# FVA-NET.net
KiCad netlist of a schematic drawn in Altium Designer
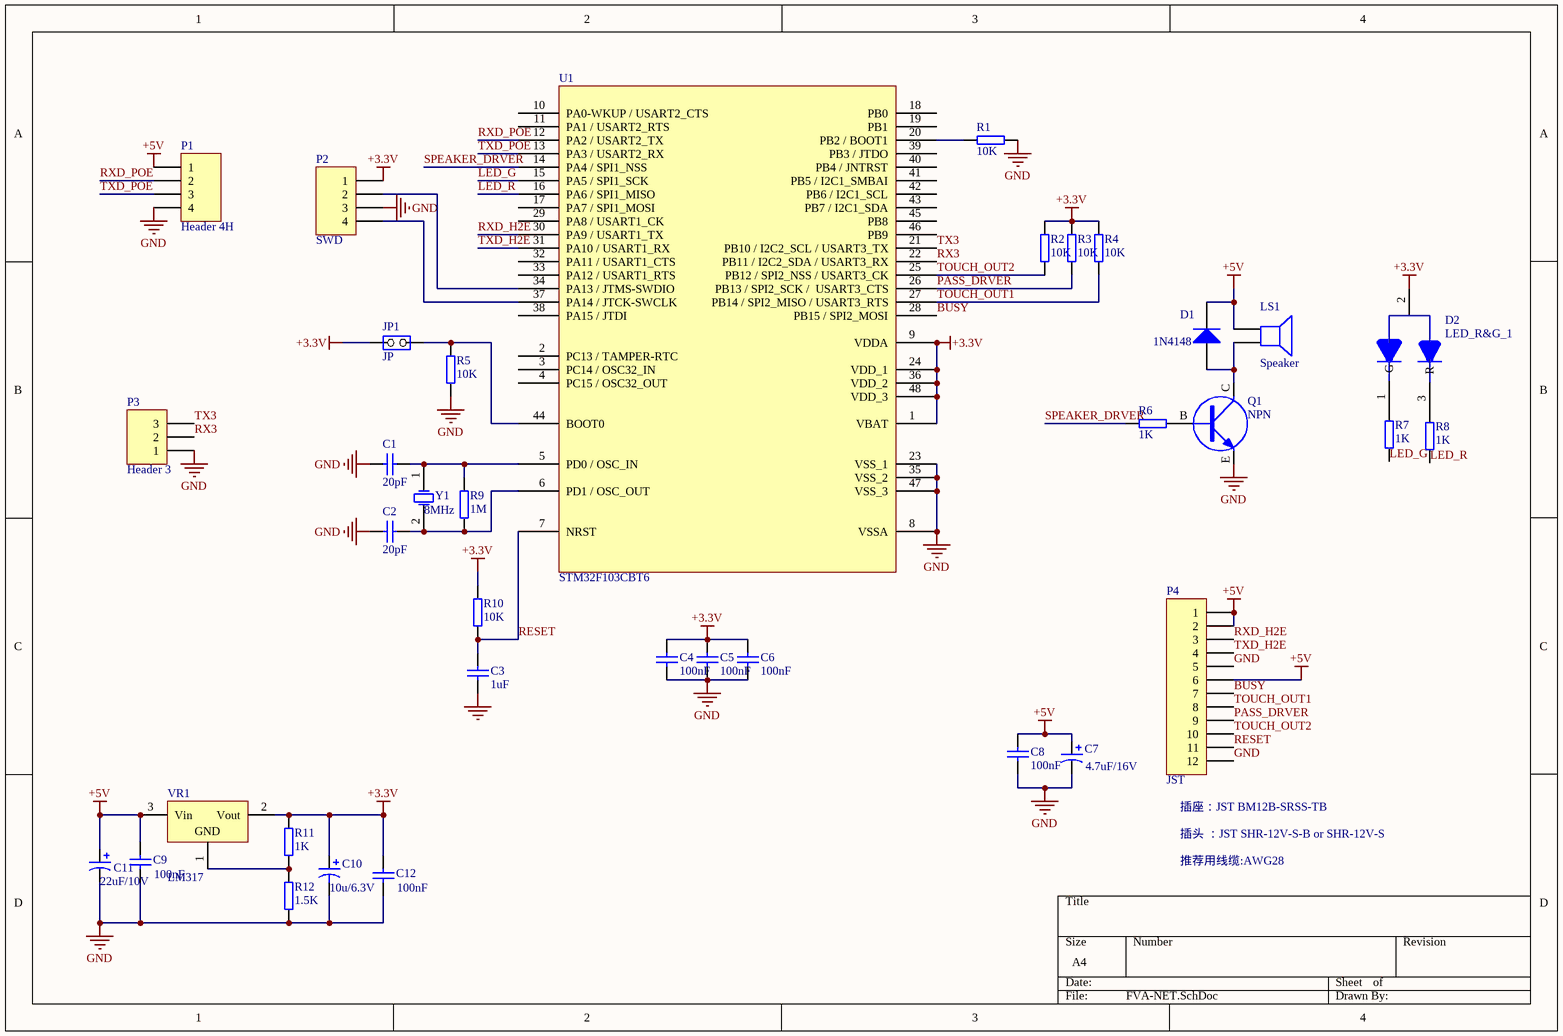
[diagram p0: FVA-NET.SchDoc]

(export (version "E")
  (design (tool "Eeschema 10.0.6"))
  (components
    (comp (ref "C1")
      (value "20pF")
      (footprint "c0603")
      (description "电容器 Capacitor")
      (fields (field (name "Comment") "Cap") (field (name "PUBLISHER") "Altium Limited"))
      (libsource (lib "电容器") (part "Cap"))
    )
    (comp (ref "C2")
      (value "20pF")
      (footprint "c0603")
      (description "电容器 Capacitor")
      (fields (field (name "Comment") "Cap") (field (name "PUBLISHER") "Altium Limited"))
      (libsource (lib "电容器") (part "Cap"))
    )
    (comp (ref "C3")
      (value "1uF")
      (footprint "c0603")
      (description "电容器 Capacitor")
      (fields (field (name "Comment") "Cap") (field (name "PUBLISHER") "Altium Limited"))
      (libsource (lib "电容器") (part "Cap"))
    )
    (comp (ref "C4")
      (value "100nF")
      (footprint "c0603")
      (description "电容器 Capacitor")
      (fields (field (name "Comment") "Cap") (field (name "PUBLISHER") "Altium Limited"))
      (libsource (lib "电容器") (part "Cap"))
    )
    (comp (ref "C5")
      (value "100nF")
      (footprint "c0603")
      (description "电容器 Capacitor")
      (fields (field (name "Comment") "Cap") (field (name "PUBLISHER") "Altium Limited"))
      (libsource (lib "电容器") (part "Cap"))
    )
    (comp (ref "C6")
      (value "100nF")
      (footprint "c0603")
      (description "电容器 Capacitor")
      (fields (field (name "Comment") "Cap") (field (name "PUBLISHER") "Altium Limited"))
      (libsource (lib "电容器") (part "Cap"))
    )
    (comp (ref "C7")
      (value "4.7uF/16V")
      (footprint "T3216")
      (fields (field (name "Comment") "CAP+"))
      (libsource (lib "PV") (part "CAP+"))
    )
    (comp (ref "C8")
      (value "100nF")
      (footprint "C0603")
      (description "Capacitor")
      (fields (field (name "Comment") "CAP"))
      (libsource (lib "PV") (part "CAP"))
    )
    (comp (ref "C9")
      (value "100nF")
      (footprint "C0603")
      (description "Capacitor")
      (fields (field (name "Comment") "cap"))
      (libsource (lib "PV") (part "CAP"))
    )
    (comp (ref "C10")
      (value "10u/6.3V")
      (footprint "T3216")
      (description "Polarized Capacitor (Radial)")
      (fields (field (name "Comment") "Cap Pol1") (field (name "PUBLISHER") "Altium Limited"))
      (libsource (lib "Miscellaneous Devices") (part "Cap Pol1"))
    )
    (comp (ref "C11")
      (value "22uF/10V")
      (footprint "T3216")
      (fields (field (name "Comment") "CAP+"))
      (libsource (lib "PV") (part "CAP+"))
    )
    (comp (ref "C12")
      (value "100nF")
      (footprint "C0603")
      (description "Capacitor")
      (fields (field (name "Comment") "cap"))
      (libsource (lib "PV") (part "CAP"))
    )
    (comp (ref "D1")
      (value "1N4148")
      (footprint "D1206")
      (description "High Conductance Fast Diode")
      (libsource (lib "Miscellaneous Devices") (part "Diode 1N4148"))
    )
    (comp (ref "D2") (value "LED_R&G_1") (footprint "LED_R&G") (libsource (lib "PV") (part "LED_R&G_1")))
    (comp (ref "JP1") (value "JP") (footprint "SIP2") (libsource (lib "开关和继电器") (part "JP2")))
    (comp (ref "LS1")
      (value "Speaker")
      (footprint "BUZZER")
      (description "Loudspeaker")
      (fields (field (name "PUBLISHER") "Altium Limited"))
      (libsource (lib "Miscellaneous Devices") (part "Speaker"))
    )
    (comp (ref "P1")
      (value "Header 4H")
      (footprint "HDR1X4H")
      (description "Header, 4-Pin, Right Angle")
      (fields (field (name "PUBLISHER") "Altium Limited"))
      (libsource (lib "Miscellaneous Connectors") (part "Header 4H"))
    )
    (comp (ref "P2")
      (value "SWD")
      (footprint "HDR1X4")
      (description "Header, 4-Pin")
      (fields (field (name "PUBLISHER") "Altium Limited"))
      (libsource (lib "Miscellaneous Connectors") (part "Header 4"))
    )
    (comp (ref "P3")
      (value "Header 3")
      (footprint "HDR1X3")
      (description "Header, 3-Pin")
      (fields (field (name "PUBLISHER") "Altium Limited"))
      (libsource (lib "Miscellaneous Connectors") (part "Header 3"))
    )
    (comp (ref "P4")
      (value "JST")
      (footprint "JST BM12B-SRSS-TB")
      (description "Header, 12-Pin")
      (fields (field (name "PUBLISHER") "Altium Limited"))
      (libsource (lib "Miscellaneous Connectors") (part "Header 12"))
    )
    (comp (ref "Q1")
      (value "NPN")
      (footprint "SOT23/BEC")
      (description "NPN Transistor")
      (libsource (lib "PV") (part "NPN"))
    )
    (comp (ref "R1")
      (value "10K")
      (footprint "R0603")
      (fields (field (name "Comment") "RES"))
      (libsource (lib "PV") (part "RES"))
    )
    (comp (ref "R2")
      (value "10K")
      (footprint "R0603")
      (fields (field (name "Comment") "RES"))
      (libsource (lib "PV") (part "RES"))
    )
    (comp (ref "R3")
      (value "10K")
      (footprint "R0603")
      (fields (field (name "Comment") "RES"))
      (libsource (lib "PV") (part "RES"))
    )
    (comp (ref "R4")
      (value "10K")
      (footprint "R0603")
      (fields (field (name "Comment") "RES"))
      (libsource (lib "PV") (part "RES"))
    )
    (comp (ref "R5")
      (value "10K")
      (footprint "R0603")
      (fields (field (name "Comment") "RES"))
      (libsource (lib "PV") (part "RES"))
    )
    (comp (ref "R6")
      (value "1K")
      (footprint "R0603")
      (fields (field (name "Comment") "RES"))
      (libsource (lib "PV") (part "RES"))
    )
    (comp (ref "R7")
      (value "1K")
      (footprint "R0603")
      (fields (field (name "Comment") "RES"))
      (libsource (lib "PV") (part "RES"))
    )
    (comp (ref "R8")
      (value "1K")
      (footprint "R0603")
      (fields (field (name "Comment") "RES"))
      (libsource (lib "PV") (part "RES"))
    )
    (comp (ref "R9")
      (value "1M")
      (footprint "R0603")
      (fields (field (name "Comment") "RES"))
      (libsource (lib "PV") (part "RES"))
    )
    (comp (ref "R10")
      (value "10K")
      (footprint "R0603")
      (fields (field (name "Comment") "RES"))
      (libsource (lib "PV") (part "RES"))
    )
    (comp (ref "R11")
      (value "1K")
      (footprint "R0603")
      (fields (field (name "Comment") "RES"))
      (libsource (lib "PV") (part "RES"))
    )
    (comp (ref "R12")
      (value "1.5K")
      (footprint "R0603")
      (fields (field (name "Comment") "RES"))
      (libsource (lib "PV") (part "RES"))
    )
    (comp (ref "U1")
      (value "STM32F103CBT6")
      (footprint "LQFP48")
      (description "48 pin")
      (libsource (lib "微控制器") (part "STM32F103x6x8xB"))
    )
    (comp (ref "VR1")
      (value "LM317")
      (footprint "SOT223")
      (description "Voltage Regulator")
      (fields (field (name "PUBLISHER") "Altium Limited"))
      (libsource (lib "FVA-NET") (part "Volt Reg"))
    )
    (comp (ref "Y1")
      (value "8MHz")
      (footprint "XTAL-HC-49/U-S")
      (description "Crystal Oscillator")
      (fields (field (name "PUBLISHER") "Altium Limited"))
      (libsource (lib "晶体_振荡器") (part "XTAL"))
    )
  )
  (nets
    (net (code "1") (name "+3.3V") (class "Default")
      (node (ref "C10") (pin "1") (pinfunction "1_1") (pintype "passive"))
      (node (ref "C12") (pin "2") (pinfunction "2_2") (pintype "passive"))
      (node (ref "C4") (pin "2") (pinfunction "2_2") (pintype "passive"))
      (node (ref "C5") (pin "2") (pinfunction "2_2") (pintype "passive"))
      (node (ref "C6") (pin "2") (pinfunction "2_2") (pintype "passive"))
      (node (ref "D2") (pin "2") (pinfunction "P_2") (pintype "passive"))
      (node (ref "JP1") (pin "1") (pinfunction "COMMON_1") (pintype "passive"))
      (node (ref "P2") (pin "1") (pinfunction "1_1") (pintype "passive"))
      (node (ref "R10") (pin "1") (pinfunction "1_1") (pintype "passive"))
      (node (ref "R11") (pin "2") (pinfunction "2_2") (pintype "passive"))
      (node (ref "R2") (pin "2") (pinfunction "2_2") (pintype "passive"))
      (node (ref "R3") (pin "2") (pinfunction "2_2") (pintype "passive"))
      (node (ref "R4") (pin "2") (pinfunction "2_2") (pintype "passive"))
      (node (ref "U1") (pin "1") (pinfunction "VBAT_1") (pintype "passive"))
      (node (ref "U1") (pin "24") (pinfunction "VDD_1_24") (pintype "passive"))
      (node (ref "U1") (pin "36") (pinfunction "VDD_2_36") (pintype "passive"))
      (node (ref "U1") (pin "48") (pinfunction "VDD_3_48") (pintype "passive"))
      (node (ref "U1") (pin "9") (pinfunction "VDDA_9") (pintype "passive"))
      (node (ref "VR1") (pin "2") (pinfunction "Vout_2") (pintype "passive"))
    )
    (net (code "2") (name "+5V") (class "Default")
      (node (ref "C11") (pin "1") (pinfunction "1_1") (pintype "passive"))
      (node (ref "C7") (pin "1") (pinfunction "1_1") (pintype "passive"))
      (node (ref "C8") (pin "2") (pinfunction "2_2") (pintype "passive"))
      (node (ref "C9") (pin "2") (pinfunction "2_2") (pintype "passive"))
      (node (ref "D1") (pin "2") (pinfunction "K_2") (pintype "passive"))
      (node (ref "LS1") (pin "1") (pinfunction "1_1") (pintype "passive"))
      (node (ref "P1") (pin "1") (pinfunction "1_1") (pintype "passive"))
      (node (ref "P4") (pin "1") (pinfunction "1_1") (pintype "passive"))
      (node (ref "P4") (pin "2") (pinfunction "2_2") (pintype "passive"))
      (node (ref "P4") (pin "6") (pinfunction "6_6") (pintype "passive"))
      (node (ref "VR1") (pin "3") (pinfunction "Vin_3") (pintype "passive"))
    )
    (net (code "3") (name "/BUSY") (class "Default")
      (node (ref "P4") (pin "7") (pinfunction "7_7") (pintype "passive"))
      (node (ref "U1") (pin "28") (pinfunction "PB15_/_SPI2_MOSI_28") (pintype "passive"))
    )
    (net (code "4") (name "/LED_G") (class "Default")
      (node (ref "R7") (pin "2") (pinfunction "2_2") (pintype "passive"))
      (node (ref "U1") (pin "15") (pinfunction "PA5_/_SPI1_SCK_15") (pintype "passive"))
    )
    (net (code "5") (name "/LED_R") (class "Default")
      (node (ref "R8") (pin "2") (pinfunction "2_2") (pintype "passive"))
      (node (ref "U1") (pin "16") (pinfunction "PA6_/_SPI1_MISO_16") (pintype "passive"))
    )
    (net (code "6") (name "/PASS_DRVER") (class "Default")
      (node (ref "P4") (pin "9") (pinfunction "9_9") (pintype "passive"))
      (node (ref "R3") (pin "1") (pinfunction "1_1") (pintype "passive"))
      (node (ref "U1") (pin "26") (pinfunction "PB13_/_SPI2_SCK_/__USART3_CTS_26") (pintype "passive"))
    )
    (net (code "7") (name "/RESET") (class "Default")
      (node (ref "C3") (pin "2") (pinfunction "2_2") (pintype "passive"))
      (node (ref "P4") (pin "11") (pinfunction "11_11") (pintype "passive"))
      (node (ref "R10") (pin "2") (pinfunction "2_2") (pintype "passive"))
      (node (ref "U1") (pin "7") (pinfunction "NRST_7") (pintype "passive"))
    )
    (net (code "8") (name "/RX3") (class "Default")
      (node (ref "P3") (pin "2") (pinfunction "2_2") (pintype "passive"))
      (node (ref "U1") (pin "22") (pinfunction "PB11_/_I2C2_SDA_/_USART3_RX_22") (pintype "passive"))
    )
    (net (code "9") (name "/RXD_H2E") (class "Default")
      (node (ref "P4") (pin "3") (pinfunction "3_3") (pintype "passive"))
      (node (ref "U1") (pin "30") (pinfunction "PA9_/_USART1_TX_30") (pintype "passive"))
    )
    (net (code "10") (name "/RXD_POE") (class "Default")
      (node (ref "P1") (pin "2") (pinfunction "2_2") (pintype "passive"))
      (node (ref "U1") (pin "12") (pinfunction "PA2_/_USART2_TX_12") (pintype "passive"))
    )
    (net (code "11") (name "/SPEAKER_DRVER") (class "Default")
      (node (ref "R6") (pin "2") (pinfunction "2_2") (pintype "passive"))
      (node (ref "U1") (pin "14") (pinfunction "PA4_/_SPI1_NSS_14") (pintype "passive"))
    )
    (net (code "12") (name "/TOUCH_OUT1") (class "Default")
      (node (ref "P4") (pin "8") (pinfunction "8_8") (pintype "passive"))
      (node (ref "R4") (pin "1") (pinfunction "1_1") (pintype "passive"))
      (node (ref "U1") (pin "27") (pinfunction "PB14_/_SPI2_MISO_/_USART3_RTS_27") (pintype "passive"))
    )
    (net (code "13") (name "/TOUCH_OUT2") (class "Default")
      (node (ref "P4") (pin "10") (pinfunction "10_10") (pintype "passive"))
      (node (ref "R2") (pin "1") (pinfunction "1_1") (pintype "passive"))
      (node (ref "U1") (pin "25") (pinfunction "PB12_/_SPI2_NSS_/_USART3_CK_25") (pintype "passive"))
    )
    (net (code "14") (name "/TX3") (class "Default")
      (node (ref "P3") (pin "3") (pinfunction "3_3") (pintype "passive"))
      (node (ref "U1") (pin "21") (pinfunction "PB10_/_I2C2_SCL_/_USART3_TX_21") (pintype "passive"))
    )
    (net (code "15") (name "/TXD_H2E") (class "Default")
      (node (ref "P4") (pin "4") (pinfunction "4_4") (pintype "passive"))
      (node (ref "U1") (pin "31") (pinfunction "PA10_/_USART1_RX_31") (pintype "passive"))
    )
    (net (code "16") (name "/TXD_POE") (class "Default")
      (node (ref "P1") (pin "3") (pinfunction "3_3") (pintype "passive"))
      (node (ref "U1") (pin "13") (pinfunction "PA3_/_USART2_RX_13") (pintype "passive"))
    )
    (net (code "17") (name "GND") (class "Default")
      (node (ref "C1") (pin "1") (pinfunction "1_1") (pintype "passive"))
      (node (ref "C10") (pin "2") (pinfunction "2_2") (pintype "passive"))
      (node (ref "C11") (pin "2") (pinfunction "2_2") (pintype "passive"))
      (node (ref "C12") (pin "1") (pinfunction "1_1") (pintype "passive"))
      (node (ref "C2") (pin "1") (pinfunction "1_1") (pintype "passive"))
      (node (ref "C3") (pin "1") (pinfunction "1_1") (pintype "passive"))
      (node (ref "C4") (pin "1") (pinfunction "1_1") (pintype "passive"))
      (node (ref "C5") (pin "1") (pinfunction "1_1") (pintype "passive"))
      (node (ref "C6") (pin "1") (pinfunction "1_1") (pintype "passive"))
      (node (ref "C7") (pin "2") (pinfunction "2_2") (pintype "passive"))
      (node (ref "C8") (pin "1") (pinfunction "1_1") (pintype "passive"))
      (node (ref "C9") (pin "1") (pinfunction "1_1") (pintype "passive"))
      (node (ref "P1") (pin "4") (pinfunction "4_4") (pintype "passive"))
      (node (ref "P2") (pin "3") (pinfunction "3_3") (pintype "passive"))
      (node (ref "P3") (pin "1") (pinfunction "1_1") (pintype "passive"))
      (node (ref "P4") (pin "12") (pinfunction "12_12") (pintype "passive"))
      (node (ref "P4") (pin "5") (pinfunction "5_5") (pintype "passive"))
      (node (ref "Q1") (pin "E") (pinfunction "E_E") (pintype "passive"))
      (node (ref "R1") (pin "1") (pinfunction "1_1") (pintype "passive"))
      (node (ref "R12") (pin "1") (pinfunction "1_1") (pintype "passive"))
      (node (ref "R5") (pin "1") (pinfunction "1_1") (pintype "passive"))
      (node (ref "U1") (pin "23") (pinfunction "VSS_1_23") (pintype "passive"))
      (node (ref "U1") (pin "35") (pinfunction "VSS_2_35") (pintype "passive"))
      (node (ref "U1") (pin "47") (pinfunction "VSS_3_47") (pintype "passive"))
      (node (ref "U1") (pin "8") (pinfunction "VSSA_8") (pintype "passive"))
    )
    (net (code "18") (name "Net-(D1-A)") (class "Default")
      (node (ref "D1") (pin "1") (pinfunction "A_1") (pintype "passive"))
      (node (ref "LS1") (pin "2") (pinfunction "2_2") (pintype "passive"))
      (node (ref "Q1") (pin "C") (pinfunction "C_C") (pintype "passive"))
    )
    (net (code "19") (name "Net-(D2-G)") (class "Default")
      (node (ref "D2") (pin "1") (pinfunction "G_1") (pintype "passive"))
      (node (ref "R7") (pin "1") (pinfunction "1_1") (pintype "passive"))
    )
    (net (code "20") (name "Net-(D2-R)") (class "Default")
      (node (ref "D2") (pin "3") (pinfunction "R_3") (pintype "passive"))
      (node (ref "R8") (pin "1") (pinfunction "1_1") (pintype "passive"))
    )
    (net (code "21") (name "Net-(JP1-NO)") (class "Default")
      (node (ref "JP1") (pin "2") (pinfunction "NO_2") (pintype "passive"))
      (node (ref "R5") (pin "2") (pinfunction "2_2") (pintype "passive"))
      (node (ref "U1") (pin "44") (pinfunction "BOOT0_44") (pintype "passive"))
    )
    (net (code "22") (name "Net-(Q1-PadB)") (class "Default")
      (node (ref "Q1") (pin "B") (pinfunction "B_B") (pintype "passive"))
      (node (ref "R6") (pin "1") (pinfunction "1_1") (pintype "passive"))
    )
    (net (code "23") (name "Net-(U1-PA13_{slash}_JTMS-SWDIO)") (class "Default")
      (node (ref "P2") (pin "2") (pinfunction "2_2") (pintype "passive"))
      (node (ref "U1") (pin "34") (pinfunction "PA13_/_JTMS-SWDIO_34") (pintype "passive"))
    )
    (net (code "24") (name "Net-(U1-PA14_{slash}_JTCK-SWCLK)") (class "Default")
      (node (ref "P2") (pin "4") (pinfunction "4_4") (pintype "passive"))
      (node (ref "U1") (pin "37") (pinfunction "PA14_/_JTCK-SWCLK_37") (pintype "passive"))
    )
    (net (code "25") (name "Net-(U1-PB2_{slash}_BOOT1)") (class "Default")
      (node (ref "R1") (pin "2") (pinfunction "2_2") (pintype "passive"))
      (node (ref "U1") (pin "20") (pinfunction "PB2_/_BOOT1_20") (pintype "passive"))
    )
    (net (code "26") (name "Net-(U1-PD0_{slash}_OSC_IN)") (class "Default")
      (node (ref "C1") (pin "2") (pinfunction "2_2") (pintype "passive"))
      (node (ref "R9") (pin "2") (pinfunction "2_2") (pintype "passive"))
      (node (ref "U1") (pin "5") (pinfunction "PD0_/_OSC_IN_5") (pintype "passive"))
      (node (ref "Y1") (pin "1") (pinfunction "OSC1_1") (pintype "passive"))
    )
    (net (code "27") (name "Net-(U1-PD1_{slash}_OSC_OUT)") (class "Default")
      (node (ref "C2") (pin "2") (pinfunction "2_2") (pintype "passive"))
      (node (ref "R9") (pin "1") (pinfunction "1_1") (pintype "passive"))
      (node (ref "U1") (pin "6") (pinfunction "PD1_/_OSC_OUT_6") (pintype "passive"))
      (node (ref "Y1") (pin "2") (pinfunction "OSC2_2") (pintype "passive"))
    )
    (net (code "28") (name "Net-(VR1-GND)") (class "Default")
      (node (ref "R11") (pin "1") (pinfunction "1_1") (pintype "passive"))
      (node (ref "R12") (pin "2") (pinfunction "2_2") (pintype "passive"))
      (node (ref "VR1") (pin "1") (pinfunction "GND_1") (pintype "passive"))
    )
    (net (code "29") (name "unconnected-(U1-PA0-WKUP_{slash}_USART2_CTS-Pad10)") (class "Default")
      (node (ref "U1") (pin "10") (pinfunction "PA0-WKUP_/_USART2_CTS_10") (pintype "passive"))
    )
    (net (code "30") (name "unconnected-(U1-PA1_{slash}_USART2_RTS-Pad11)") (class "Default")
      (node (ref "U1") (pin "11") (pinfunction "PA1_/_USART2_RTS_11") (pintype "passive"))
    )
    (net (code "31") (name "unconnected-(U1-PA7_{slash}_SPI1_MOSI-Pad17)") (class "Default")
      (node (ref "U1") (pin "17") (pinfunction "PA7_/_SPI1_MOSI_17") (pintype "passive"))
    )
    (net (code "32") (name "unconnected-(U1-PA8_{slash}_USART1_CK-Pad29)") (class "Default")
      (node (ref "U1") (pin "29") (pinfunction "PA8_/_USART1_CK_29") (pintype "passive"))
    )
    (net (code "33") (name "unconnected-(U1-PA11_{slash}_USART1_CTS-Pad32)") (class "Default")
      (node (ref "U1") (pin "32") (pinfunction "PA11_/_USART1_CTS_32") (pintype "passive"))
    )
    (net (code "34") (name "unconnected-(U1-PA12_{slash}_USART1_RTS-Pad33)") (class "Default")
      (node (ref "U1") (pin "33") (pinfunction "PA12_/_USART1_RTS_33") (pintype "passive"))
    )
    (net (code "35") (name "unconnected-(U1-PA15_{slash}_JTDI-Pad38)") (class "Default")
      (node (ref "U1") (pin "38") (pinfunction "PA15_/_JTDI_38") (pintype "passive"))
    )
    (net (code "36") (name "unconnected-(U1-PB0-Pad18)") (class "Default")
      (node (ref "U1") (pin "18") (pinfunction "PB0_18") (pintype "passive"))
    )
    (net (code "37") (name "unconnected-(U1-PB1-Pad19)") (class "Default")
      (node (ref "U1") (pin "19") (pinfunction "PB1_19") (pintype "passive"))
    )
    (net (code "38") (name "unconnected-(U1-PB3_{slash}_JTDO-Pad39)") (class "Default")
      (node (ref "U1") (pin "39") (pinfunction "PB3_/_JTDO_39") (pintype "passive"))
    )
    (net (code "39") (name "unconnected-(U1-PB4_{slash}_JNTRST-Pad40)") (class "Default")
      (node (ref "U1") (pin "40") (pinfunction "PB4_/_JNTRST_40") (pintype "passive"))
    )
    (net (code "40") (name "unconnected-(U1-PB5_{slash}_I2C1_SMBAI-Pad41)") (class "Default")
      (node (ref "U1") (pin "41") (pinfunction "PB5_/_I2C1_SMBAI_41") (pintype "passive"))
    )
    (net (code "41") (name "unconnected-(U1-PB6_{slash}_I2C1_SCL-Pad42)") (class "Default")
      (node (ref "U1") (pin "42") (pinfunction "PB6_/_I2C1_SCL_42") (pintype "passive"))
    )
    (net (code "42") (name "unconnected-(U1-PB7_{slash}_I2C1_SDA-Pad43)") (class "Default")
      (node (ref "U1") (pin "43") (pinfunction "PB7_/_I2C1_SDA_43") (pintype "passive"))
    )
    (net (code "43") (name "unconnected-(U1-PB8-Pad45)") (class "Default")
      (node (ref "U1") (pin "45") (pinfunction "PB8_45") (pintype "passive"))
    )
    (net (code "44") (name "unconnected-(U1-PB9-Pad46)") (class "Default")
      (node (ref "U1") (pin "46") (pinfunction "PB9_46") (pintype "passive"))
    )
    (net (code "45") (name "unconnected-(U1-PC13_{slash}_TAMPER-RTC-Pad2)") (class "Default")
      (node (ref "U1") (pin "2") (pinfunction "PC13_/_TAMPER-RTC_2") (pintype "passive"))
    )
    (net (code "46") (name "unconnected-(U1-PC14_{slash}_OSC32_IN-Pad3)") (class "Default")
      (node (ref "U1") (pin "3") (pinfunction "PC14_/_OSC32_IN_3") (pintype "passive"))
    )
    (net (code "47") (name "unconnected-(U1-PC15_{slash}_OSC32_OUT-Pad4)") (class "Default")
      (node (ref "U1") (pin "4") (pinfunction "PC15_/_OSC32_OUT_4") (pintype "passive"))
    )
  )
)
